# Connections.net
KiCad netlist of a schematic drawn in Altium Designer
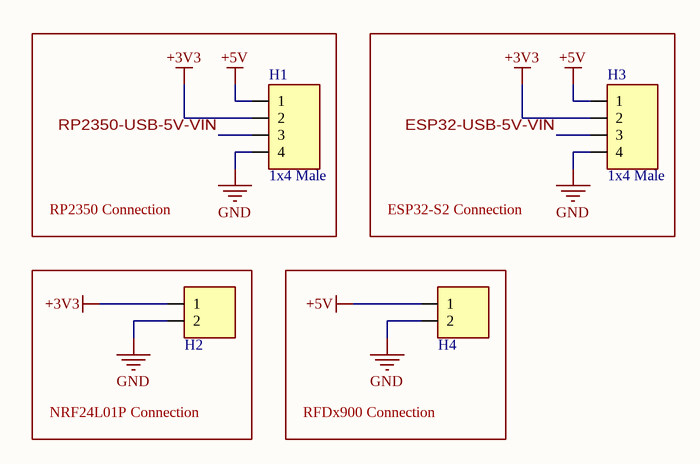
[diagram p0: Connections.SchDoc]

(export (version "E")
  (design (tool "Eeschema 10.0.6"))
  (components
    (comp (ref "H1")
      (value "1x4 Male")
      (footprint "[Header] Shrouded 1x4 Male")
      (description "70543-0003\r\nMates with 005057-9404")
      (libsource (lib "RADM Connectors") (part "[Header] Shrouded 1x4 Male"))
    )
    (comp (ref "H2")
      (value "1x2 Male")
      (footprint "[Header] Shrouded 1x2 Male")
      (description "0705430036\r\nMates with 0050579402")
      (libsource (lib "RADM Connectors") (part "[Header] Shrouded 1x2 Male"))
    )
    (comp (ref "H3")
      (value "1x4 Male")
      (footprint "[Header] Shrouded 1x4 Male")
      (description "70543-0003\r\nMates with 005057-9404")
      (libsource (lib "RADM Connectors") (part "[Header] Shrouded 1x4 Male"))
    )
    (comp (ref "H4")
      (value "1x2 Male")
      (footprint "[Header] Shrouded 1x2 Male")
      (description "0705430036\r\nMates with 0050579402")
      (libsource (lib "RADM Connectors") (part "[Header] Shrouded 1x2 Male"))
    )
  )
  (nets
    (net (code "1") (name "+3V3") (class "Default")
      (node (ref "H1") (pin "2") (pinfunction "2_2") (pintype "passive"))
      (node (ref "H2") (pin "1") (pinfunction "1_1") (pintype "passive"))
      (node (ref "H3") (pin "2") (pinfunction "2_2") (pintype "passive"))
    )
    (net (code "2") (name "+5V") (class "Default")
      (node (ref "H1") (pin "1") (pinfunction "1_1") (pintype "passive"))
      (node (ref "H3") (pin "1") (pinfunction "1_1") (pintype "passive"))
      (node (ref "H4") (pin "1") (pinfunction "1_1") (pintype "passive"))
    )
    (net (code "3") (name "/ESP32-USB-5V-VIN") (class "Default")
      (node (ref "H3") (pin "3") (pinfunction "3_3") (pintype "passive"))
    )
    (net (code "4") (name "/RP2350-USB-5V-VIN") (class "Default")
      (node (ref "H1") (pin "3") (pinfunction "3_3") (pintype "passive"))
    )
    (net (code "5") (name "GND") (class "Default")
      (node (ref "H1") (pin "4") (pinfunction "4_4") (pintype "passive"))
      (node (ref "H2") (pin "2") (pinfunction "2_2") (pintype "passive"))
      (node (ref "H3") (pin "4") (pinfunction "4_4") (pintype "passive"))
      (node (ref "H4") (pin "2") (pinfunction "2_2") (pintype "passive"))
    )
  )
)
